# tx_train.net
KiCad netlist of a schematic drawn in EAGLE
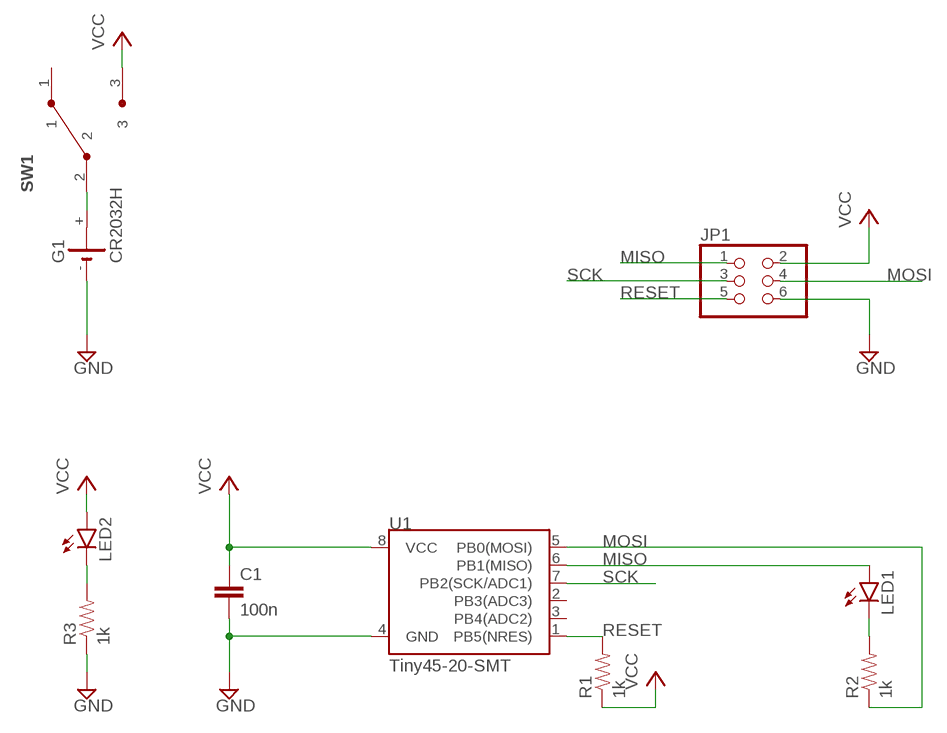
[diagram p0: schematic, sheet 1]

(export (version "E")
  (design (tool "Eeschema 10.0.6"))
  (components
    (comp (ref "C1")
      (value "100n")
      (footprint "eagle-import:0603-CAP")
      (libsource (lib "eagle-import") (part "CAP0603-CAP"))
    )
    (comp (ref "G1")
      (value "CR2032H")
      (footprint "eagle-import:CR2032H")
      (libsource (lib "eagle-import") (part "CR2032H"))
    )
    (comp (ref "JP1")
      (value "PINHD-2X3")
      (footprint "eagle-import:2X03")
      (libsource (lib "eagle-import") (part "PINHD-2X3"))
    )
    (comp (ref "LED1")
      (value "LED3MM")
      (footprint "eagle-import:LED3MM")
      (libsource (lib "eagle-import") (part "LED3MM"))
    )
    (comp (ref "LED2")
      (value "LED0603")
      (footprint "eagle-import:LED-0603")
      (libsource (lib "eagle-import") (part "LED0603"))
    )
    (comp (ref "R1")
      (value "1k")
      (footprint "eagle-import:0603-RES")
      (libsource (lib "eagle-import") (part "RESISTOR0603"))
    )
    (comp (ref "R2")
      (value "1k")
      (footprint "eagle-import:0603-RES")
      (libsource (lib "eagle-import") (part "RESISTOR0603"))
    )
    (comp (ref "R3")
      (value "1k")
      (footprint "eagle-import:0603-RES")
      (libsource (lib "eagle-import") (part "RESISTOR0603"))
    )
    (comp (ref "SW1")
      (value "JS102011SAQN")
      (footprint "eagle-import:JS102011SAQN")
      (libsource (lib "eagle-import") (part "JS102011SAQN"))
    )
    (comp (ref "U1")
      (value "Tiny45-20-SMT")
      (footprint "eagle-import:SO08-EIAJ")
      (libsource (lib "eagle-import") (part "ATTINY45TINY45-20-SMT"))
    )
  )
  (nets
    (net (code "1") (name "/MISO") (class "Default")
      (node (ref "JP1") (pin "1") (pinfunction "1_1") (pintype "passive"))
      (node (ref "LED1") (pin "A") (pinfunction "A_A") (pintype "passive"))
      (node (ref "U1") (pin "6") (pinfunction "PB1(MISO)_6") (pintype "bidirectional"))
    )
    (net (code "2") (name "/MOSI") (class "Default")
      (node (ref "JP1") (pin "4") (pinfunction "4_4") (pintype "passive"))
      (node (ref "R2") (pin "1") (pinfunction "1_1") (pintype "passive"))
      (node (ref "U1") (pin "5") (pinfunction "PB0(MOSI)_5") (pintype "bidirectional"))
    )
    (net (code "3") (name "/RESET") (class "Default")
      (node (ref "JP1") (pin "5") (pinfunction "5_5") (pintype "passive"))
      (node (ref "R1") (pin "2") (pinfunction "2_2") (pintype "passive"))
      (node (ref "U1") (pin "1") (pinfunction "PB5(NRES)_1") (pintype "bidirectional"))
    )
    (net (code "4") (name "/SCK") (class "Default")
      (node (ref "JP1") (pin "3") (pinfunction "3_3") (pintype "passive"))
      (node (ref "U1") (pin "7") (pinfunction "PB2(SCK/ADC1)_7") (pintype "bidirectional"))
    )
    (net (code "5") (name "GND") (class "Default")
      (node (ref "C1") (pin "2") (pinfunction "2_2") (pintype "passive"))
      (node (ref "G1") (pin "-") (pinfunction "-_-") (pintype "passive"))
      (node (ref "JP1") (pin "6") (pinfunction "6_6") (pintype "passive"))
      (node (ref "R3") (pin "1") (pinfunction "1_1") (pintype "passive"))
      (node (ref "U1") (pin "4") (pinfunction "GND_4") (pintype "bidirectional"))
    )
    (net (code "6") (name "Net-(G1-Pad+)") (class "Default")
      (node (ref "G1") (pin "+") (pinfunction "+_+") (pintype "passive"))
      (node (ref "SW1") (pin "2") (pinfunction "2_2") (pintype "bidirectional"))
    )
    (net (code "7") (name "Net-(LED1-C)") (class "Default")
      (node (ref "LED1") (pin "K") (pinfunction "C_K") (pintype "passive"))
      (node (ref "R2") (pin "2") (pinfunction "2_2") (pintype "passive"))
    )
    (net (code "8") (name "Net-(LED2-PadC)") (class "Default")
      (node (ref "LED2") (pin "C") (pinfunction "C_C") (pintype "passive"))
      (node (ref "R3") (pin "2") (pinfunction "2_2") (pintype "passive"))
    )
    (net (code "9") (name "VCC") (class "Default")
      (node (ref "C1") (pin "1") (pinfunction "1_1") (pintype "passive"))
      (node (ref "JP1") (pin "2") (pinfunction "2_2") (pintype "passive"))
      (node (ref "LED2") (pin "A") (pinfunction "A_A") (pintype "passive"))
      (node (ref "R1") (pin "1") (pinfunction "1_1") (pintype "passive"))
      (node (ref "SW1") (pin "3") (pinfunction "3_3") (pintype "bidirectional"))
      (node (ref "U1") (pin "8") (pinfunction "VCC_8") (pintype "bidirectional"))
    )
    (net (code "10") (name "unconnected-(G1-+-Pad+@1)") (class "Default")
      (node (ref "G1") (pin "+@1") (pinfunction "+_+@1") (pintype "passive"))
    )
    (net (code "11") (name "unconnected-(SW1-Pad1)") (class "Default")
      (node (ref "SW1") (pin "1") (pinfunction "1_1") (pintype "bidirectional"))
    )
    (net (code "12") (name "unconnected-(U1-PB3(ADC3)-Pad2)") (class "Default")
      (node (ref "U1") (pin "2") (pinfunction "PB3(ADC3)_2") (pintype "bidirectional"))
    )
    (net (code "13") (name "unconnected-(U1-PB4(ADC2)-Pad3)") (class "Default")
      (node (ref "U1") (pin "3") (pinfunction "PB4(ADC2)_3") (pintype "bidirectional"))
    )
  )
)
